# Example_Board_To_Convert.net
KiCad netlist of a schematic drawn in EAGLE
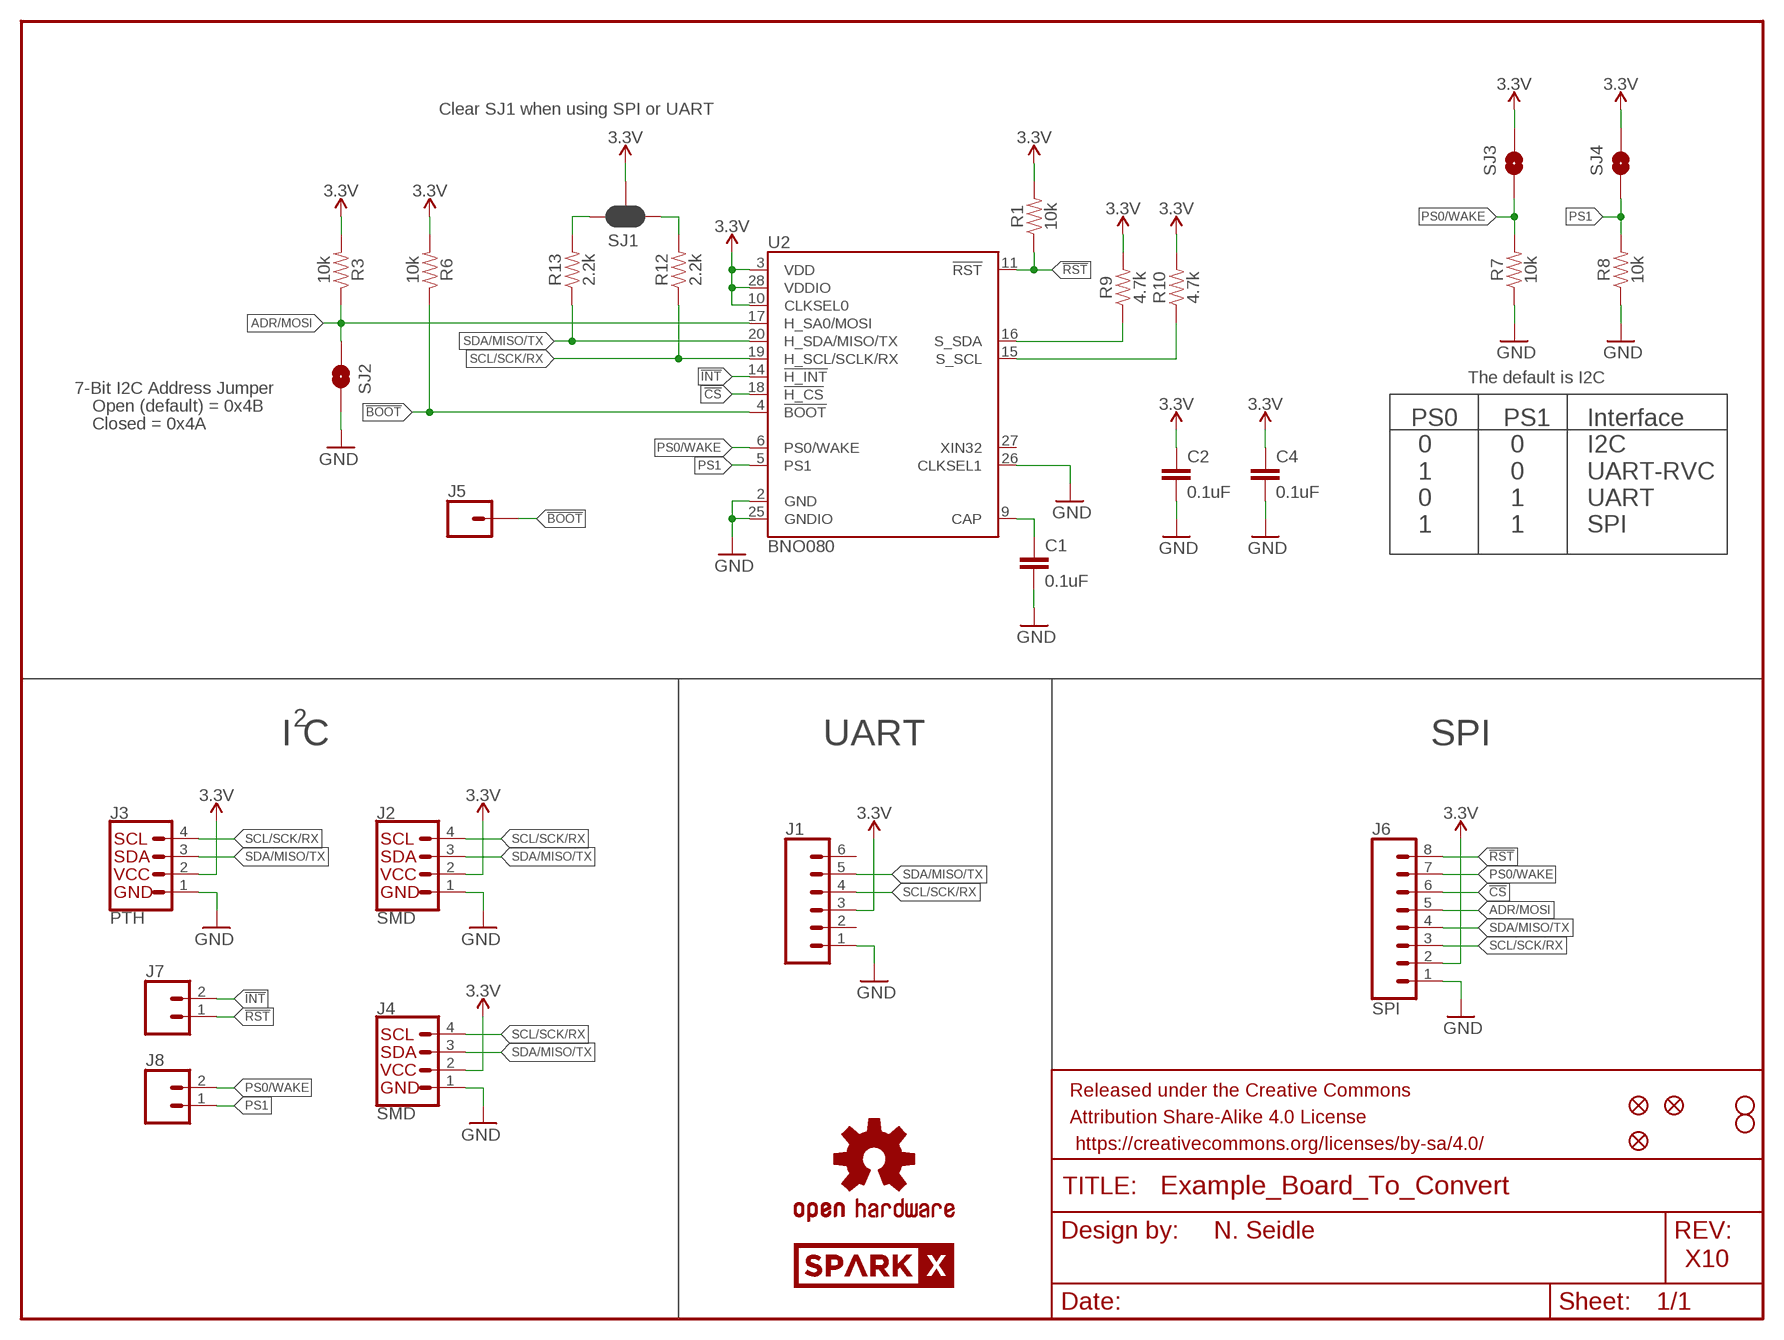
[diagram p0: schematic, sheet 1]

(export (version "E")
  (design (tool "Eeschema 10.0.6"))
  (components
    (comp (ref "C1")
      (value "0.1uF")
      (footprint "eagle-import:0603")
      (libsource (lib "eagle-import") (part "0.1UF-0603-25V-(+80/-20%)"))
    )
    (comp (ref "C2")
      (value "0.1uF")
      (footprint "eagle-import:0603")
      (libsource (lib "eagle-import") (part "0.1UF-0603-25V-(+80/-20%)"))
    )
    (comp (ref "C4")
      (value "0.1uF")
      (footprint "eagle-import:0603")
      (libsource (lib "eagle-import") (part "0.1UF-0603-25V-(+80/-20%)"))
    )
    (comp (ref "FRAME1")
      (value "FRAME-LETTER")
      (footprint "eagle-import:CREATIVE_COMMONS")
      (libsource (lib "eagle-import") (part "FRAME-LETTER"))
    )
    (comp (ref "J1")
      (value "CONN_06NO_SILK_FEMALE_PTH")
      (footprint "eagle-import:1X06_NO_SILK")
      (libsource (lib "eagle-import") (part "CONN_06NO_SILK_FEMALE_PTH"))
    )
    (comp (ref "J2")
      (value "SMD")
      (footprint "eagle-import:1X04_1MM_RA")
      (libsource (lib "eagle-import") (part "I2C_STANDARDJS-1MM"))
    )
    (comp (ref "J3")
      (value "PTH")
      (footprint "eagle-import:1X04_NO_SILK")
      (libsource (lib "eagle-import") (part "I2C_STANDARD_NO_SILK"))
    )
    (comp (ref "J4")
      (value "SMD")
      (footprint "eagle-import:1X04_1MM_RA")
      (libsource (lib "eagle-import") (part "I2C_STANDARDJS-1MM"))
    )
    (comp (ref "J5")
      (value "CONN_01PTH_NO_SILK_YES_STOP")
      (footprint "eagle-import:1X01_NO_SILK")
      (libsource (lib "eagle-import") (part "CONN_01PTH_NO_SILK_YES_STOP"))
    )
    (comp (ref "J6")
      (value "SPI")
      (footprint "eagle-import:1X08_NO_SILK")
      (libsource (lib "eagle-import") (part "CONN_08NO_SILK_FEMALE_PTH"))
    )
    (comp (ref "J7")
      (value "CONN_021X02_NO_SILK")
      (footprint "eagle-import:1X02_NO_SILK")
      (libsource (lib "eagle-import") (part "CONN_021X02_NO_SILK"))
    )
    (comp (ref "J8")
      (value "CONN_021X02_NO_SILK")
      (footprint "eagle-import:1X02_NO_SILK")
      (libsource (lib "eagle-import") (part "CONN_021X02_NO_SILK"))
    )
    (comp (ref "JP1")
      (value "FIDUCIALUFIDUCIAL")
      (footprint "eagle-import:MICRO-FIDUCIAL")
      (libsource (lib "eagle-import") (part "FIDUCIALUFIDUCIAL"))
    )
    (comp (ref "JP2")
      (value "FIDUCIALUFIDUCIAL")
      (footprint "eagle-import:MICRO-FIDUCIAL")
      (libsource (lib "eagle-import") (part "FIDUCIALUFIDUCIAL"))
    )
    (comp (ref "JP3")
      (value "STAND-OFF")
      (footprint "eagle-import:STAND-OFF")
      (libsource (lib "eagle-import") (part "STAND-OFF"))
    )
    (comp (ref "JP4")
      (value "STAND-OFF")
      (footprint "eagle-import:STAND-OFF")
      (libsource (lib "eagle-import") (part "STAND-OFF"))
    )
    (comp (ref "JP6")
      (value "FIDUCIALUFIDUCIAL")
      (footprint "eagle-import:MICRO-FIDUCIAL")
      (libsource (lib "eagle-import") (part "FIDUCIALUFIDUCIAL"))
    )
    (comp (ref "LOGO1")
      (value "OSHW-LOGOMINI")
      (footprint "eagle-import:OSHW-LOGO-MINI")
      (libsource (lib "eagle-import") (part "OSHW-LOGOMINI"))
    )
    (comp (ref "R1")
      (value "10k")
      (footprint "eagle-import:0603")
      (libsource (lib "eagle-import") (part "10KOHM-0603-1/10W-1%"))
    )
    (comp (ref "R3")
      (value "10k")
      (footprint "eagle-import:0603")
      (libsource (lib "eagle-import") (part "10KOHM-0603-1/10W-1%"))
    )
    (comp (ref "R6")
      (value "10k")
      (footprint "eagle-import:0603")
      (libsource (lib "eagle-import") (part "10KOHM-0603-1/10W-1%"))
    )
    (comp (ref "R7")
      (value "10k")
      (footprint "eagle-import:0603")
      (libsource (lib "eagle-import") (part "10KOHM-0603-1/10W-1%"))
    )
    (comp (ref "R8")
      (value "10k")
      (footprint "eagle-import:0603")
      (libsource (lib "eagle-import") (part "10KOHM-0603-1/10W-1%"))
    )
    (comp (ref "R9")
      (value "4.7k")
      (footprint "eagle-import:0603")
      (libsource (lib "eagle-import") (part "4.7KOHM-0603-1/10W-1%"))
    )
    (comp (ref "R10")
      (value "4.7k")
      (footprint "eagle-import:0603")
      (libsource (lib "eagle-import") (part "4.7KOHM-0603-1/10W-1%"))
    )
    (comp (ref "R12")
      (value "2.2k")
      (footprint "eagle-import:0603")
      (libsource (lib "eagle-import") (part "2.2KOHM-0603-1/10W-1%"))
    )
    (comp (ref "R13")
      (value "2.2k")
      (footprint "eagle-import:0603")
      (libsource (lib "eagle-import") (part "2.2KOHM-0603-1/10W-1%"))
    )
    (comp (ref "SJ1")
      (value "JUMPER-SMT_3_2-NC_PASTE_SILK")
      (footprint "eagle-import:SMT-JUMPER_3_2-NC_PASTE_SILK")
      (libsource (lib "eagle-import") (part "JUMPER-SMT_3_2-NC_PASTE_SILK"))
    )
    (comp (ref "SJ2")
      (value "SOLDERJUMPERNO")
      (footprint "eagle-import:SJ_2S-NO")
      (libsource (lib "eagle-import") (part "SOLDERJUMPERNO"))
    )
    (comp (ref "SJ3")
      (value "SOLDERJUMPERNO")
      (footprint "eagle-import:SJ_2S-NO")
      (libsource (lib "eagle-import") (part "SOLDERJUMPERNO"))
    )
    (comp (ref "SJ4")
      (value "SOLDERJUMPERNO")
      (footprint "eagle-import:SJ_2S-NO")
      (libsource (lib "eagle-import") (part "SOLDERJUMPERNO"))
    )
    (comp (ref "U$1")
      (value "SPARKX-LOGO3")
      (footprint "eagle-import:SPARKX-SMALL")
      (libsource (lib "eagle-import") (part "SPARKX-LOGO3"))
    )
    (comp (ref "U$2")
      (value "SPARKX-LOGO3")
      (footprint "eagle-import:SPARKX-SMALL")
      (libsource (lib "eagle-import") (part "SPARKX-LOGO3"))
    )
    (comp (ref "U2")
      (value "BNO080")
      (footprint "eagle-import:LGA-28")
      (libsource (lib "eagle-import") (part "BNO080"))
    )
  )
  (nets
    (net (code "1") (name "/~{BOOT}") (class "Default")
      (node (ref "J5") (pin "1") (pinfunction "1_1") (pintype "passive"))
      (node (ref "R6") (pin "1") (pinfunction "1_1") (pintype "passive"))
      (node (ref "U2") (pin "4") (pinfunction "~{BOOT}_4") (pintype "bidirectional"))
    )
    (net (code "2") (name "/~{CS}") (class "Default")
      (node (ref "J6") (pin "6") (pinfunction "6_6") (pintype "passive"))
      (node (ref "U2") (pin "18") (pinfunction "~{H_CS}_18") (pintype "bidirectional"))
    )
    (net (code "3") (name "/~{INT}") (class "Default")
      (node (ref "J7") (pin "2") (pinfunction "2_2") (pintype "passive"))
      (node (ref "U2") (pin "14") (pinfunction "~{H_INT}_14") (pintype "bidirectional"))
    )
    (net (code "4") (name "/~{RST}") (class "Default")
      (node (ref "J6") (pin "8") (pinfunction "8_8") (pintype "passive"))
      (node (ref "J7") (pin "1") (pinfunction "1_1") (pintype "passive"))
      (node (ref "R1") (pin "1") (pinfunction "1_1") (pintype "passive"))
      (node (ref "U2") (pin "11") (pinfunction "~{RST}_11") (pintype "bidirectional"))
    )
    (net (code "5") (name "3.3V") (class "Default")
      (node (ref "C2") (pin "1") (pinfunction "1_1") (pintype "passive"))
      (node (ref "C4") (pin "1") (pinfunction "1_1") (pintype "passive"))
      (node (ref "J1") (pin "3") (pinfunction "3_3") (pintype "passive"))
      (node (ref "J2") (pin "2") (pinfunction "VCC_2") (pintype "power_in"))
      (node (ref "J3") (pin "2") (pinfunction "VCC_2") (pintype "power_in"))
      (node (ref "J4") (pin "2") (pinfunction "VCC_2") (pintype "power_in"))
      (node (ref "J6") (pin "2") (pinfunction "2_2") (pintype "passive"))
      (node (ref "R1") (pin "2") (pinfunction "2_2") (pintype "passive"))
      (node (ref "R10") (pin "2") (pinfunction "2_2") (pintype "passive"))
      (node (ref "R3") (pin "2") (pinfunction "2_2") (pintype "passive"))
      (node (ref "R6") (pin "2") (pinfunction "2_2") (pintype "passive"))
      (node (ref "R9") (pin "2") (pinfunction "2_2") (pintype "passive"))
      (node (ref "SJ1") (pin "2") (pinfunction "2_2") (pintype "passive"))
      (node (ref "SJ3") (pin "1") (pinfunction "1_1") (pintype "passive"))
      (node (ref "SJ4") (pin "1") (pinfunction "1_1") (pintype "passive"))
      (node (ref "U2") (pin "10") (pinfunction "CLKSEL0_10") (pintype "bidirectional"))
      (node (ref "U2") (pin "28") (pinfunction "VDDIO_28") (pintype "bidirectional"))
      (node (ref "U2") (pin "3") (pinfunction "VDD_3") (pintype "bidirectional"))
    )
    (net (code "6") (name "ADR{slash}MOSI") (class "Default")
      (node (ref "J6") (pin "5") (pinfunction "5_5") (pintype "passive"))
      (node (ref "R3") (pin "1") (pinfunction "1_1") (pintype "passive"))
      (node (ref "SJ2") (pin "2") (pinfunction "2_2") (pintype "passive"))
      (node (ref "U2") (pin "17") (pinfunction "H_SA0/MOSI_17") (pintype "bidirectional"))
    )
    (net (code "7") (name "GND") (class "Default")
      (node (ref "C1") (pin "2") (pinfunction "2_2") (pintype "passive"))
      (node (ref "C2") (pin "2") (pinfunction "2_2") (pintype "passive"))
      (node (ref "C4") (pin "2") (pinfunction "2_2") (pintype "passive"))
      (node (ref "J1") (pin "1") (pinfunction "1_1") (pintype "passive"))
      (node (ref "J2") (pin "1") (pinfunction "GND_1") (pintype "power_in"))
      (node (ref "J3") (pin "1") (pinfunction "GND_1") (pintype "power_in"))
      (node (ref "J4") (pin "1") (pinfunction "GND_1") (pintype "power_in"))
      (node (ref "J6") (pin "1") (pinfunction "1_1") (pintype "passive"))
      (node (ref "R7") (pin "1") (pinfunction "1_1") (pintype "passive"))
      (node (ref "R8") (pin "1") (pinfunction "1_1") (pintype "passive"))
      (node (ref "SJ2") (pin "1") (pinfunction "1_1") (pintype "passive"))
      (node (ref "U2") (pin "2") (pinfunction "GND_2") (pintype "bidirectional"))
      (node (ref "U2") (pin "25") (pinfunction "GNDIO_25") (pintype "bidirectional"))
      (node (ref "U2") (pin "26") (pinfunction "CLKSEL1_26") (pintype "bidirectional"))
    )
    (net (code "8") (name "Net-(R12-Pad2)") (class "Default")
      (node (ref "R12") (pin "2") (pinfunction "2_2") (pintype "passive"))
      (node (ref "SJ1") (pin "1") (pinfunction "1_1") (pintype "passive"))
    )
    (net (code "9") (name "Net-(R13-Pad2)") (class "Default")
      (node (ref "R13") (pin "2") (pinfunction "2_2") (pintype "passive"))
      (node (ref "SJ1") (pin "3") (pinfunction "3_3") (pintype "passive"))
    )
    (net (code "10") (name "Net-(U2-CAP)") (class "Default")
      (node (ref "C1") (pin "1") (pinfunction "1_1") (pintype "passive"))
      (node (ref "U2") (pin "9") (pinfunction "CAP_9") (pintype "bidirectional"))
    )
    (net (code "11") (name "Net-(U2-S_SCL)") (class "Default")
      (node (ref "R10") (pin "1") (pinfunction "1_1") (pintype "passive"))
      (node (ref "U2") (pin "15") (pinfunction "S_SCL_15") (pintype "bidirectional"))
    )
    (net (code "12") (name "Net-(U2-S_SDA)") (class "Default")
      (node (ref "R9") (pin "1") (pinfunction "1_1") (pintype "passive"))
      (node (ref "U2") (pin "16") (pinfunction "S_SDA_16") (pintype "bidirectional"))
    )
    (net (code "13") (name "PS0{slash}WAKE") (class "Default")
      (node (ref "J6") (pin "7") (pinfunction "7_7") (pintype "passive"))
      (node (ref "J8") (pin "2") (pinfunction "2_2") (pintype "passive"))
      (node (ref "R7") (pin "2") (pinfunction "2_2") (pintype "passive"))
      (node (ref "SJ3") (pin "2") (pinfunction "2_2") (pintype "passive"))
      (node (ref "U2") (pin "6") (pinfunction "PS0/WAKE_6") (pintype "bidirectional"))
    )
    (net (code "14") (name "PS1") (class "Default")
      (node (ref "J8") (pin "1") (pinfunction "1_1") (pintype "passive"))
      (node (ref "R8") (pin "2") (pinfunction "2_2") (pintype "passive"))
      (node (ref "SJ4") (pin "2") (pinfunction "2_2") (pintype "passive"))
      (node (ref "U2") (pin "5") (pinfunction "PS1_5") (pintype "bidirectional"))
    )
    (net (code "15") (name "SCL{slash}SCK{slash}RX") (class "Default")
      (node (ref "J1") (pin "4") (pinfunction "4_4") (pintype "passive"))
      (node (ref "J2") (pin "4") (pinfunction "SCL_4") (pintype "passive"))
      (node (ref "J3") (pin "4") (pinfunction "SCL_4") (pintype "passive"))
      (node (ref "J4") (pin "4") (pinfunction "SCL_4") (pintype "passive"))
      (node (ref "J6") (pin "3") (pinfunction "3_3") (pintype "passive"))
      (node (ref "R12") (pin "1") (pinfunction "1_1") (pintype "passive"))
      (node (ref "U2") (pin "19") (pinfunction "H_SCL/SCLK/RX_19") (pintype "bidirectional"))
    )
    (net (code "16") (name "SDA{slash}MISO{slash}TX") (class "Default")
      (node (ref "J1") (pin "5") (pinfunction "5_5") (pintype "passive"))
      (node (ref "J2") (pin "3") (pinfunction "SDA_3") (pintype "passive"))
      (node (ref "J3") (pin "3") (pinfunction "SDA_3") (pintype "passive"))
      (node (ref "J4") (pin "3") (pinfunction "SDA_3") (pintype "passive"))
      (node (ref "J6") (pin "4") (pinfunction "4_4") (pintype "passive"))
      (node (ref "R13") (pin "1") (pinfunction "1_1") (pintype "passive"))
      (node (ref "U2") (pin "20") (pinfunction "H_SDA/MISO/TX_20") (pintype "bidirectional"))
    )
    (net (code "17") (name "unconnected-(J1-Pad2)") (class "Default")
      (node (ref "J1") (pin "2") (pinfunction "2_2") (pintype "passive"))
    )
    (net (code "18") (name "unconnected-(J1-Pad6)") (class "Default")
      (node (ref "J1") (pin "6") (pinfunction "6_6") (pintype "passive"))
    )
    (net (code "19") (name "unconnected-(U2-XIN32-Pad27)") (class "Default")
      (node (ref "U2") (pin "27") (pinfunction "XIN32_27") (pintype "bidirectional"))
    )
  )
)
